# linearSensor.net
KiCad netlist of a schematic drawn in EAGLE
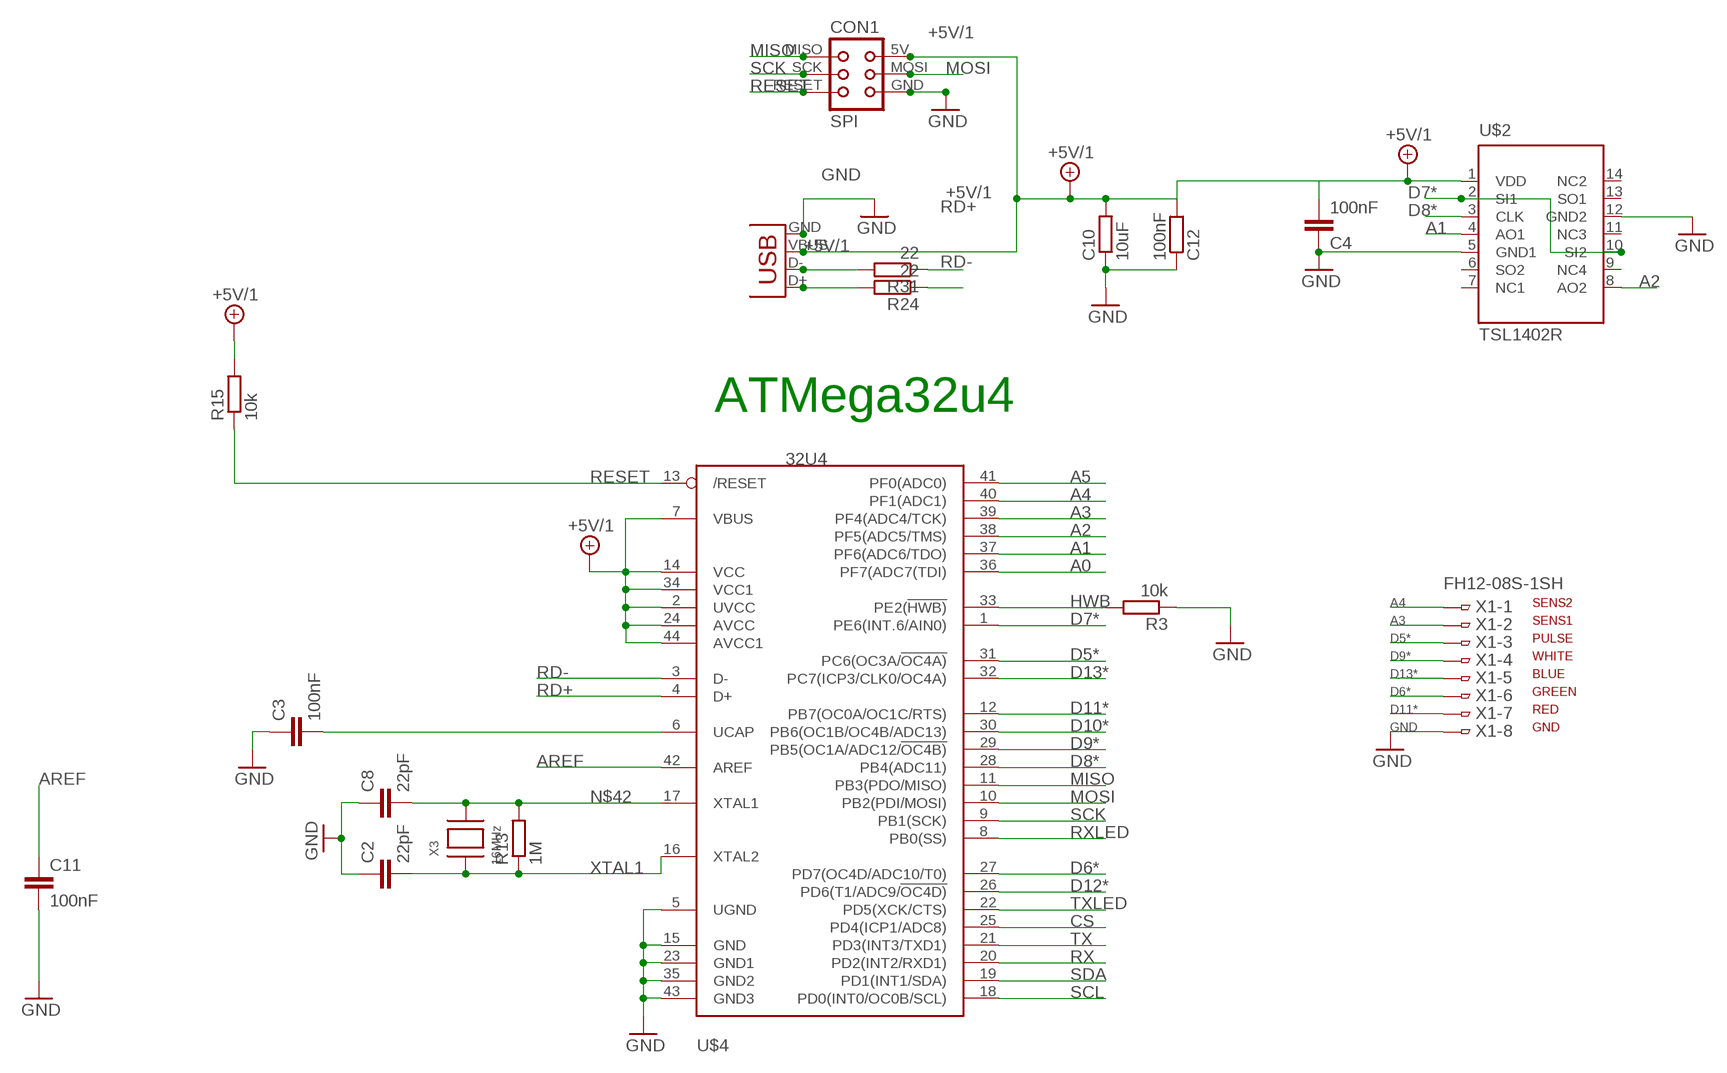
[diagram p0: schematic, sheet 1]

(export (version "E")
  (design (tool "Eeschema 10.0.6"))
  (components
    (comp (ref "C2")
      (value "22pF")
      (footprint "eagle-import:C0805K")
      (libsource (lib "eagle-import") (part "C-EUC0805K"))
    )
    (comp (ref "C3")
      (value "100nF")
      (footprint "eagle-import:C0805K")
      (libsource (lib "eagle-import") (part "C-EUC0805K"))
    )
    (comp (ref "C4")
      (value "100nF")
      (footprint "eagle-import:C0805")
      (libsource (lib "eagle-import") (part "C-EUC0805"))
    )
    (comp (ref "C8")
      (value "22pF")
      (footprint "eagle-import:C0805K")
      (libsource (lib "eagle-import") (part "C-EUC0805K"))
    )
    (comp (ref "C10")
      (value "10uF")
      (footprint "eagle-import:M0805")
      (libsource (lib "eagle-import") (part "R-EU_M0805"))
    )
    (comp (ref "C11")
      (value "100nF")
      (footprint "eagle-import:C0805K")
      (libsource (lib "eagle-import") (part "C-EUC0805K"))
    )
    (comp (ref "C12")
      (value "100nF")
      (footprint "eagle-import:M0805")
      (libsource (lib "eagle-import") (part "R-EU_M0805"))
    )
    (comp (ref "CON1")
      (value "SPI")
      (footprint "eagle-import:TC2030-MCP-NL")
      (libsource (lib "eagle-import") (part "TINYISPT"))
    )
    (comp (ref "R3")
      (value "10k")
      (footprint "eagle-import:M0805")
      (libsource (lib "eagle-import") (part "resistor_R-EU_M0805"))
    )
    (comp (ref "R13")
      (value "1M")
      (footprint "eagle-import:M0805")
      (libsource (lib "eagle-import") (part "R-EU_M0805"))
    )
    (comp (ref "R15")
      (value "10k")
      (footprint "eagle-import:M0805")
      (libsource (lib "eagle-import") (part "resistor_R-EU_M0805"))
    )
    (comp (ref "R24")
      (value "22")
      (footprint "eagle-import:M0805")
      (libsource (lib "eagle-import") (part "R-EU_M0805"))
    )
    (comp (ref "R31")
      (value "22")
      (footprint "eagle-import:M0805")
      (libsource (lib "eagle-import") (part "R-EU_M0805"))
    )
    (comp (ref "U$2")
      (value "TSL1402R")
      (footprint "eagle-import:DIL14")
      (libsource (lib "eagle-import") (part "TSL1402R"))
    )
    (comp (ref "U$4")
      (value "32U4")
      (footprint "eagle-import:TQFP44")
      (libsource (lib "eagle-import") (part "ATMEGA32U4-AU"))
    )
    (comp (ref "X1")
      (value "FH12-08S-1SH")
      (footprint "eagle-import:FH12-08S-1SH")
      (libsource (lib "eagle-import") (part "FH12-08S-1SH"))
    )
    (comp (ref "X2")
      (value "USB-MICROB")
      (footprint "eagle-import:USB-MICROB")
      (libsource (lib "eagle-import") (part "USB-MICROB"))
    )
    (comp (ref "X3")
      (value "16MHz")
      (footprint "eagle-import:NX6035")
      (libsource (lib "eagle-import") (part "XTALNX6035"))
    )
  )
  (nets
    (net (code "1") (name "+5V{slash}1") (class "Default")
      (node (ref "C10") (pin "2") (pinfunction "2_2") (pintype "passive"))
      (node (ref "C12") (pin "2") (pinfunction "2_2") (pintype "passive"))
      (node (ref "C4") (pin "2") (pinfunction "2_2") (pintype "passive"))
      (node (ref "CON1") (pin "5V") (pinfunction "VCC_5V") (pintype "passive"))
      (node (ref "R15") (pin "2") (pinfunction "2_2") (pintype "passive"))
      (node (ref "U$2") (pin "1") (pinfunction "VDD_1") (pintype "power_in"))
      (node (ref "U$4") (pin "14") (pinfunction "VCC_14") (pintype "bidirectional"))
      (node (ref "U$4") (pin "2") (pinfunction "UVCC_2") (pintype "bidirectional"))
      (node (ref "U$4") (pin "24") (pinfunction "AVCC_24") (pintype "bidirectional"))
      (node (ref "U$4") (pin "34") (pinfunction "VCC1_34") (pintype "bidirectional"))
      (node (ref "U$4") (pin "44") (pinfunction "AVCC1_44") (pintype "bidirectional"))
      (node (ref "U$4") (pin "7") (pinfunction "VBUS_7") (pintype "bidirectional"))
      (node (ref "X2") (pin "VBUS") (pinfunction "VBUS_VBUS") (pintype "bidirectional"))
    )
    (net (code "2") (name "/A0") (class "Default")
      (node (ref "U$4") (pin "36") (pinfunction "PF7(ADC7(TDI)_36") (pintype "bidirectional"))
    )
    (net (code "3") (name "/A1") (class "Default")
      (node (ref "U$2") (pin "4") (pinfunction "AO1_4") (pintype "output"))
      (node (ref "U$4") (pin "37") (pinfunction "PF6(ADC6/TDO)_37") (pintype "bidirectional"))
    )
    (net (code "4") (name "/A2") (class "Default")
      (node (ref "U$2") (pin "8") (pinfunction "AO2_8") (pintype "output"))
      (node (ref "U$4") (pin "38") (pinfunction "PF5(ADC5/TMS)_38") (pintype "bidirectional"))
    )
    (net (code "5") (name "/A3") (class "Default")
      (node (ref "U$4") (pin "39") (pinfunction "PF4(ADC4/TCK)_39") (pintype "bidirectional"))
      (node (ref "X1") (pin "2") (pinfunction "1_2") (pintype "passive"))
    )
    (net (code "6") (name "/A4") (class "Default")
      (node (ref "U$4") (pin "40") (pinfunction "PF1(ADC1)_40") (pintype "bidirectional"))
      (node (ref "X1") (pin "1") (pinfunction "1_1") (pintype "passive"))
    )
    (net (code "7") (name "/A5") (class "Default")
      (node (ref "U$4") (pin "41") (pinfunction "PF0(ADC0)_41") (pintype "bidirectional"))
    )
    (net (code "8") (name "/AREF") (class "Default")
      (node (ref "C11") (pin "1") (pinfunction "1_1") (pintype "passive"))
      (node (ref "U$4") (pin "42") (pinfunction "AREF_42") (pintype "bidirectional"))
    )
    (net (code "9") (name "/CS") (class "Default")
      (node (ref "U$4") (pin "25") (pinfunction "PD4(ICP1/ADC8)_25") (pintype "bidirectional"))
    )
    (net (code "10") (name "/D5*") (class "Default")
      (node (ref "U$4") (pin "31") (pinfunction "PC6(OC3A/~{OC4A})_31") (pintype "bidirectional"))
      (node (ref "X1") (pin "3") (pinfunction "1_3") (pintype "passive"))
    )
    (net (code "11") (name "/D6*") (class "Default")
      (node (ref "U$4") (pin "27") (pinfunction "PD7(OC4D/ADC10/T0)_27") (pintype "bidirectional"))
      (node (ref "X1") (pin "6") (pinfunction "1_6") (pintype "passive"))
    )
    (net (code "12") (name "/D7*") (class "Default")
      (node (ref "U$2") (pin "10") (pinfunction "SI2_10") (pintype "input"))
      (node (ref "U$2") (pin "2") (pinfunction "SI1_2") (pintype "input"))
      (node (ref "U$4") (pin "1") (pinfunction "PE6(INT.6/AIN0)_1") (pintype "bidirectional"))
    )
    (net (code "13") (name "/D8*") (class "Default")
      (node (ref "U$2") (pin "3") (pinfunction "CLK_3") (pintype "input"))
      (node (ref "U$4") (pin "28") (pinfunction "PB4(ADC11)_28") (pintype "bidirectional"))
    )
    (net (code "14") (name "/D9*") (class "Default")
      (node (ref "U$4") (pin "29") (pinfunction "PB5(OC1A/ADC12/~{OC4B})_29") (pintype "bidirectional"))
      (node (ref "X1") (pin "4") (pinfunction "1_4") (pintype "passive"))
    )
    (net (code "15") (name "/D10*") (class "Default")
      (node (ref "U$4") (pin "30") (pinfunction "PB6(OC1B/OC4B/ADC13)_30") (pintype "bidirectional"))
    )
    (net (code "16") (name "/D11*") (class "Default")
      (node (ref "U$4") (pin "12") (pinfunction "PB7(OC0A/OC1C/RTS)_12") (pintype "bidirectional"))
      (node (ref "X1") (pin "7") (pinfunction "1_7") (pintype "passive"))
    )
    (net (code "17") (name "/D12*") (class "Default")
      (node (ref "U$4") (pin "26") (pinfunction "PD6(T1/ADC9/~{OC4D})_26") (pintype "bidirectional"))
    )
    (net (code "18") (name "/D13*") (class "Default")
      (node (ref "U$4") (pin "32") (pinfunction "PC7(ICP3/CLK0/OC4A)_32") (pintype "bidirectional"))
      (node (ref "X1") (pin "5") (pinfunction "1_5") (pintype "passive"))
    )
    (net (code "19") (name "/HWB") (class "Default")
      (node (ref "R3") (pin "2") (pinfunction "2_2") (pintype "passive"))
      (node (ref "U$4") (pin "33") (pinfunction "PE2(~{HWB})_33") (pintype "bidirectional"))
    )
    (net (code "20") (name "/MISO") (class "Default")
      (node (ref "CON1") (pin "MISO") (pinfunction "MISO_MISO") (pintype "passive"))
      (node (ref "U$4") (pin "11") (pinfunction "PB3(PDO/MISO)_11") (pintype "bidirectional"))
    )
    (net (code "21") (name "/MOSI") (class "Default")
      (node (ref "CON1") (pin "MOSI") (pinfunction "MOSI_MOSI") (pintype "passive"))
      (node (ref "U$4") (pin "10") (pinfunction "PB2(PDI/MOSI)_10") (pintype "bidirectional"))
    )
    (net (code "22") (name "/N$42") (class "Default")
      (node (ref "C8") (pin "2") (pinfunction "2_2") (pintype "passive"))
      (node (ref "R13") (pin "2") (pinfunction "2_2") (pintype "passive"))
      (node (ref "U$4") (pin "17") (pinfunction "XTAL1_17") (pintype "bidirectional"))
      (node (ref "X3") (pin "P$2") (pinfunction "P$2_P$2") (pintype "bidirectional"))
    )
    (net (code "23") (name "/RD+") (class "Default")
      (node (ref "R24") (pin "1") (pinfunction "1_1") (pintype "passive"))
      (node (ref "U$4") (pin "4") (pinfunction "D+_4") (pintype "bidirectional"))
    )
    (net (code "24") (name "/RD-") (class "Default")
      (node (ref "R31") (pin "1") (pinfunction "1_1") (pintype "passive"))
      (node (ref "U$4") (pin "3") (pinfunction "D-_3") (pintype "bidirectional"))
    )
    (net (code "25") (name "/RESET") (class "Default")
      (node (ref "CON1") (pin "RESET") (pinfunction "RESET_RESET") (pintype "passive"))
      (node (ref "R15") (pin "1") (pinfunction "1_1") (pintype "passive"))
      (node (ref "U$4") (pin "13") (pinfunction "/RESET_13") (pintype "bidirectional"))
    )
    (net (code "26") (name "/RX") (class "Default")
      (node (ref "U$4") (pin "20") (pinfunction "PD2(INT2/RXD1)_20") (pintype "bidirectional"))
    )
    (net (code "27") (name "/RXLED") (class "Default")
      (node (ref "U$4") (pin "8") (pinfunction "PB0(SS)_8") (pintype "bidirectional"))
    )
    (net (code "28") (name "/SCK") (class "Default")
      (node (ref "CON1") (pin "SCK") (pinfunction "SCK_SCK") (pintype "passive"))
      (node (ref "U$4") (pin "9") (pinfunction "PB1(SCK)_9") (pintype "bidirectional"))
    )
    (net (code "29") (name "/SCL") (class "Default")
      (node (ref "U$4") (pin "18") (pinfunction "PD0(INT0/OC0B/SCL)_18") (pintype "bidirectional"))
    )
    (net (code "30") (name "/SDA") (class "Default")
      (node (ref "U$4") (pin "19") (pinfunction "PD1(INT1/SDA)_19") (pintype "bidirectional"))
    )
    (net (code "31") (name "/TX") (class "Default")
      (node (ref "U$4") (pin "21") (pinfunction "PD3(INT3/TXD1)_21") (pintype "bidirectional"))
    )
    (net (code "32") (name "/TXLED") (class "Default")
      (node (ref "U$4") (pin "22") (pinfunction "PD5(XCK/CTS)_22") (pintype "bidirectional"))
    )
    (net (code "33") (name "/XTAL1") (class "Default")
      (node (ref "C2") (pin "2") (pinfunction "2_2") (pintype "passive"))
      (node (ref "R13") (pin "1") (pinfunction "1_1") (pintype "passive"))
      (node (ref "U$4") (pin "16") (pinfunction "XTAL2_16") (pintype "bidirectional"))
      (node (ref "X3") (pin "P$1") (pinfunction "P$1_P$1") (pintype "bidirectional"))
    )
    (net (code "34") (name "GND") (class "Default")
      (node (ref "C10") (pin "1") (pinfunction "1_1") (pintype "passive"))
      (node (ref "C11") (pin "2") (pinfunction "2_2") (pintype "passive"))
      (node (ref "C12") (pin "1") (pinfunction "1_1") (pintype "passive"))
      (node (ref "C2") (pin "1") (pinfunction "1_1") (pintype "passive"))
      (node (ref "C3") (pin "1") (pinfunction "1_1") (pintype "passive"))
      (node (ref "C4") (pin "1") (pinfunction "1_1") (pintype "passive"))
      (node (ref "C8") (pin "1") (pinfunction "1_1") (pintype "passive"))
      (node (ref "CON1") (pin "GND") (pinfunction "GND_GND") (pintype "passive"))
      (node (ref "R3") (pin "1") (pinfunction "1_1") (pintype "passive"))
      (node (ref "U$2") (pin "12") (pinfunction "GND2_12") (pintype "power_in"))
      (node (ref "U$2") (pin "5") (pinfunction "GND1_5") (pintype "power_in"))
      (node (ref "U$4") (pin "15") (pinfunction "GND_15") (pintype "bidirectional"))
      (node (ref "U$4") (pin "23") (pinfunction "GND1_23") (pintype "bidirectional"))
      (node (ref "U$4") (pin "35") (pinfunction "GND2_35") (pintype "bidirectional"))
      (node (ref "U$4") (pin "43") (pinfunction "GND3_43") (pintype "bidirectional"))
      (node (ref "U$4") (pin "5") (pinfunction "UGND_5") (pintype "bidirectional"))
      (node (ref "X1") (pin "8") (pinfunction "1_8") (pintype "passive"))
      (node (ref "X2") (pin "GND") (pinfunction "GND_GND") (pintype "bidirectional"))
    )
    (net (code "35") (name "Net-(R24-Pad2)") (class "Default")
      (node (ref "R24") (pin "2") (pinfunction "2_2") (pintype "passive"))
      (node (ref "X2") (pin "D+") (pinfunction "D+_D+") (pintype "bidirectional"))
    )
    (net (code "36") (name "Net-(R31-Pad2)") (class "Default")
      (node (ref "R31") (pin "2") (pinfunction "2_2") (pintype "passive"))
      (node (ref "X2") (pin "D-") (pinfunction "D-_D-") (pintype "bidirectional"))
    )
    (net (code "37") (name "Net-(U$4-UCAP)") (class "Default")
      (node (ref "C3") (pin "2") (pinfunction "2_2") (pintype "passive"))
      (node (ref "U$4") (pin "6") (pinfunction "UCAP_6") (pintype "bidirectional"))
    )
    (net (code "38") (name "unconnected-(U$2-NC1-Pad7)") (class "Default")
      (node (ref "U$2") (pin "7") (pinfunction "NC1_7") (pintype "no_connect"))
    )
    (net (code "39") (name "unconnected-(U$2-NC2-Pad14)") (class "Default")
      (node (ref "U$2") (pin "14") (pinfunction "NC2_14") (pintype "no_connect"))
    )
    (net (code "40") (name "unconnected-(U$2-NC3-Pad11)") (class "Default")
      (node (ref "U$2") (pin "11") (pinfunction "NC3_11") (pintype "no_connect"))
    )
    (net (code "41") (name "unconnected-(U$2-NC4-Pad9)") (class "Default")
      (node (ref "U$2") (pin "9") (pinfunction "NC4_9") (pintype "no_connect"))
    )
    (net (code "42") (name "unconnected-(U$2-SO1-Pad13)") (class "Default")
      (node (ref "U$2") (pin "13") (pinfunction "SO1_13") (pintype "output"))
    )
    (net (code "43") (name "unconnected-(U$2-SO2-Pad6)") (class "Default")
      (node (ref "U$2") (pin "6") (pinfunction "SO2_6") (pintype "output"))
    )
  )
)
